# AS3364_waveform_VCA_0402_DIL_v1_0-for_de.net
KiCad netlist of a schematic drawn in EAGLE
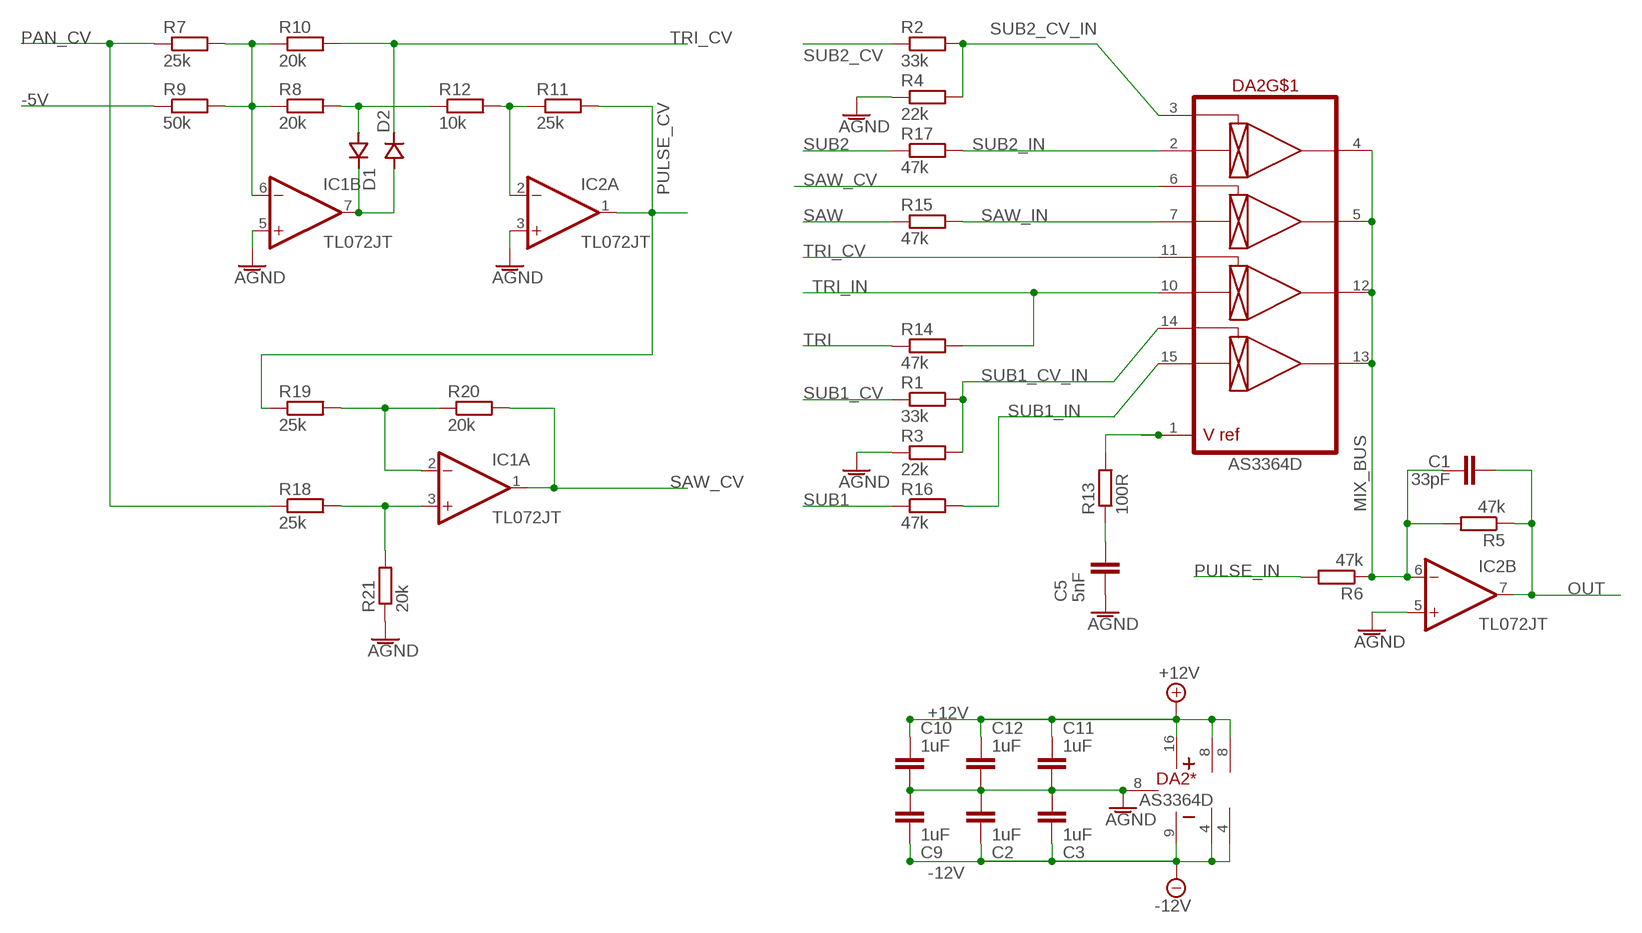
[diagram p0: schematic, sheet 1]

(export (version "E")
  (design (tool "Eeschema 10.0.6"))
  (components
    (comp (ref "C1")
      (value "33pF")
      (footprint "eagle-import:C0402-J")
      (libsource (lib "eagle-import") (part "C-EU-J"))
    )
    (comp (ref "C2")
      (value "1uF")
      (footprint "eagle-import:C0402-J")
      (libsource (lib "eagle-import") (part "C-EU-J"))
    )
    (comp (ref "C3")
      (value "1uF")
      (footprint "eagle-import:C0402-J")
      (libsource (lib "eagle-import") (part "C-EU-J"))
    )
    (comp (ref "C5")
      (value "5nF")
      (footprint "eagle-import:C0402-J")
      (libsource (lib "eagle-import") (part "C-EU-J"))
    )
    (comp (ref "C9")
      (value "1uF")
      (footprint "eagle-import:C0402-J")
      (libsource (lib "eagle-import") (part "C-EU-J"))
    )
    (comp (ref "C10")
      (value "1uF")
      (footprint "eagle-import:C0402-J")
      (libsource (lib "eagle-import") (part "C-EU-J"))
    )
    (comp (ref "C11")
      (value "1uF")
      (footprint "eagle-import:C0402-J")
      (libsource (lib "eagle-import") (part "C-EU-J"))
    )
    (comp (ref "C12")
      (value "1uF")
      (footprint "eagle-import:C0402-J")
      (libsource (lib "eagle-import") (part "C-EU-J"))
    )
    (comp (ref "D1")
      (value "DIODESOD323")
      (footprint "eagle-import:SOD323J")
      (fields (field (name "MPN") "CDSOD323-T05C"))
      (libsource (lib "eagle-import") (part "DIODESOD323"))
    )
    (comp (ref "D2")
      (value "DIODESOD323")
      (footprint "eagle-import:SOD323J")
      (fields (field (name "MPN") "CDSOD323-T05C"))
      (libsource (lib "eagle-import") (part "DIODESOD323"))
    )
    (comp (ref "DA2")
      (value "AS3364D")
      (footprint "eagle-import:DIL16J")
      (libsource (lib "eagle-import") (part "AS3364D"))
    )
    (comp (ref "IC1")
      (value "TL072JT")
      (footprint "eagle-import:TSSOP8J")
      (libsource (lib "eagle-import") (part "TL072JT"))
    )
    (comp (ref "IC2")
      (value "TL072JT")
      (footprint "eagle-import:TSSOP8J")
      (libsource (lib "eagle-import") (part "TL072JT"))
    )
    (comp (ref "R1")
      (value "33k")
      (footprint "eagle-import:R0402")
      (libsource (lib "eagle-import") (part "R-EU_R0402"))
    )
    (comp (ref "R2")
      (value "33k")
      (footprint "eagle-import:R0402")
      (libsource (lib "eagle-import") (part "R-EU_R0402"))
    )
    (comp (ref "R3")
      (value "22k")
      (footprint "eagle-import:R0402")
      (libsource (lib "eagle-import") (part "R-EU_R0402"))
    )
    (comp (ref "R4")
      (value "22k")
      (footprint "eagle-import:R0402")
      (libsource (lib "eagle-import") (part "R-EU_R0402"))
    )
    (comp (ref "R5")
      (value "47k")
      (footprint "eagle-import:R0402")
      (libsource (lib "eagle-import") (part "R-EU_R0402"))
    )
    (comp (ref "R6")
      (value "47k")
      (footprint "eagle-import:R0402")
      (libsource (lib "eagle-import") (part "R-EU_R0402"))
    )
    (comp (ref "R7")
      (value "25k")
      (footprint "eagle-import:R0402")
      (libsource (lib "eagle-import") (part "R-EU_R0402"))
    )
    (comp (ref "R8")
      (value "20k")
      (footprint "eagle-import:R0402")
      (libsource (lib "eagle-import") (part "R-EU_R0402"))
    )
    (comp (ref "R9")
      (value "50k")
      (footprint "eagle-import:R0402")
      (libsource (lib "eagle-import") (part "R-EU_R0402"))
    )
    (comp (ref "R10")
      (value "20k")
      (footprint "eagle-import:R0402")
      (libsource (lib "eagle-import") (part "R-EU_R0402"))
    )
    (comp (ref "R11")
      (value "25k")
      (footprint "eagle-import:R0402")
      (libsource (lib "eagle-import") (part "R-EU_R0402"))
    )
    (comp (ref "R12")
      (value "10k")
      (footprint "eagle-import:R0402")
      (libsource (lib "eagle-import") (part "R-EU_R0402"))
    )
    (comp (ref "R13")
      (value "100R")
      (footprint "eagle-import:R0402")
      (libsource (lib "eagle-import") (part "R-EU_R0402"))
    )
    (comp (ref "R14")
      (value "47k")
      (footprint "eagle-import:R0402")
      (libsource (lib "eagle-import") (part "R-EU_R0402"))
    )
    (comp (ref "R15")
      (value "47k")
      (footprint "eagle-import:R0402")
      (libsource (lib "eagle-import") (part "R-EU_R0402"))
    )
    (comp (ref "R16")
      (value "47k")
      (footprint "eagle-import:R0402")
      (libsource (lib "eagle-import") (part "R-EU_R0402"))
    )
    (comp (ref "R17")
      (value "47k")
      (footprint "eagle-import:R0402")
      (libsource (lib "eagle-import") (part "R-EU_R0402"))
    )
    (comp (ref "R18")
      (value "25k")
      (footprint "eagle-import:R0402")
      (libsource (lib "eagle-import") (part "R-EU_R0402"))
    )
    (comp (ref "R19")
      (value "25k")
      (footprint "eagle-import:R0402")
      (libsource (lib "eagle-import") (part "R-EU_R0402"))
    )
    (comp (ref "R20")
      (value "20k")
      (footprint "eagle-import:R0402")
      (libsource (lib "eagle-import") (part "R-EU_R0402"))
    )
    (comp (ref "R21")
      (value "20k")
      (footprint "eagle-import:R0402")
      (libsource (lib "eagle-import") (part "R-EU_R0402"))
    )
  )
  (nets
    (net (code "1") (name "+12V") (class "Default")
      (node (ref "C10") (pin "2") (pinfunction "2_2") (pintype "passive"))
      (node (ref "C11") (pin "2") (pinfunction "2_2") (pintype "passive"))
      (node (ref "C12") (pin "2") (pinfunction "2_2") (pintype "passive"))
      (node (ref "DA2") (pin "16") (pinfunction "V+_16") (pintype "power_in"))
      (node (ref "IC1") (pin "8") (pinfunction "V+_8") (pintype "power_in"))
      (node (ref "IC2") (pin "8") (pinfunction "V+_8") (pintype "power_in"))
    )
    (net (code "2") (name "-12V") (class "Default")
      (node (ref "C2") (pin "1") (pinfunction "1_1") (pintype "passive"))
      (node (ref "C3") (pin "1") (pinfunction "1_1") (pintype "passive"))
      (node (ref "C9") (pin "1") (pinfunction "1_1") (pintype "passive"))
      (node (ref "DA2") (pin "9") (pinfunction "V-_9") (pintype "power_in"))
      (node (ref "IC1") (pin "4") (pinfunction "V-_4") (pintype "power_in"))
      (node (ref "IC2") (pin "4") (pinfunction "V-_4") (pintype "power_in"))
    )
    (net (code "3") (name "/-5V") (class "Default")
      (node (ref "R9") (pin "1") (pinfunction "1_1") (pintype "passive"))
    )
    (net (code "4") (name "/MIX_BUS") (class "Default")
      (node (ref "C1") (pin "2") (pinfunction "2_2") (pintype "passive"))
      (node (ref "DA2") (pin "12") (pinfunction "OUT3_12") (pintype "output"))
      (node (ref "DA2") (pin "13") (pinfunction "OUT4_13") (pintype "output"))
      (node (ref "DA2") (pin "4") (pinfunction "OUT1_4") (pintype "output"))
      (node (ref "DA2") (pin "5") (pinfunction "OUT2_5") (pintype "output"))
      (node (ref "IC2") (pin "6") (pinfunction "-IN_6") (pintype "input"))
      (node (ref "R5") (pin "2") (pinfunction "2_2") (pintype "passive"))
      (node (ref "R6") (pin "1") (pinfunction "1_1") (pintype "passive"))
    )
    (net (code "5") (name "/OUT") (class "Default")
      (node (ref "C1") (pin "1") (pinfunction "1_1") (pintype "passive"))
      (node (ref "IC2") (pin "7") (pinfunction "OUT_7") (pintype "output"))
      (node (ref "R5") (pin "1") (pinfunction "1_1") (pintype "passive"))
    )
    (net (code "6") (name "/PAN_CV") (class "Default")
      (node (ref "R18") (pin "1") (pinfunction "1_1") (pintype "passive"))
      (node (ref "R7") (pin "1") (pinfunction "1_1") (pintype "passive"))
    )
    (net (code "7") (name "/PULSE_CV") (class "Default")
      (node (ref "IC2") (pin "1") (pinfunction "OUT_1") (pintype "output"))
      (node (ref "R11") (pin "2") (pinfunction "2_2") (pintype "passive"))
      (node (ref "R19") (pin "1") (pinfunction "1_1") (pintype "passive"))
    )
    (net (code "8") (name "/PULSE_IN") (class "Default")
      (node (ref "R6") (pin "2") (pinfunction "2_2") (pintype "passive"))
    )
    (net (code "9") (name "/SAW") (class "Default")
      (node (ref "R15") (pin "1") (pinfunction "1_1") (pintype "passive"))
    )
    (net (code "10") (name "/SAW_CV") (class "Default")
      (node (ref "DA2") (pin "6") (pinfunction "CV2_6") (pintype "input"))
      (node (ref "IC1") (pin "1") (pinfunction "OUT_1") (pintype "output"))
      (node (ref "R20") (pin "2") (pinfunction "2_2") (pintype "passive"))
    )
    (net (code "11") (name "/SAW_IN") (class "Default")
      (node (ref "DA2") (pin "7") (pinfunction "IN2_7") (pintype "input"))
      (node (ref "R15") (pin "2") (pinfunction "2_2") (pintype "passive"))
    )
    (net (code "12") (name "/SUB1") (class "Default")
      (node (ref "R16") (pin "1") (pinfunction "1_1") (pintype "passive"))
    )
    (net (code "13") (name "/SUB1_CV") (class "Default")
      (node (ref "R1") (pin "1") (pinfunction "1_1") (pintype "passive"))
    )
    (net (code "14") (name "/SUB1_CV_IN") (class "Default")
      (node (ref "DA2") (pin "14") (pinfunction "CV4_14") (pintype "input"))
      (node (ref "R1") (pin "2") (pinfunction "2_2") (pintype "passive"))
      (node (ref "R3") (pin "2") (pinfunction "2_2") (pintype "passive"))
    )
    (net (code "15") (name "/SUB1_IN") (class "Default")
      (node (ref "DA2") (pin "15") (pinfunction "IN4_15") (pintype "input"))
      (node (ref "R16") (pin "2") (pinfunction "2_2") (pintype "passive"))
    )
    (net (code "16") (name "/SUB2") (class "Default")
      (node (ref "R17") (pin "1") (pinfunction "1_1") (pintype "passive"))
    )
    (net (code "17") (name "/SUB2_CV") (class "Default")
      (node (ref "R2") (pin "1") (pinfunction "1_1") (pintype "passive"))
    )
    (net (code "18") (name "/SUB2_CV_IN") (class "Default")
      (node (ref "DA2") (pin "3") (pinfunction "CV1_3") (pintype "input"))
      (node (ref "R2") (pin "2") (pinfunction "2_2") (pintype "passive"))
      (node (ref "R4") (pin "2") (pinfunction "2_2") (pintype "passive"))
    )
    (net (code "19") (name "/SUB2_IN") (class "Default")
      (node (ref "DA2") (pin "2") (pinfunction "IN1_2") (pintype "input"))
      (node (ref "R17") (pin "2") (pinfunction "2_2") (pintype "passive"))
    )
    (net (code "20") (name "/TRI") (class "Default")
      (node (ref "R14") (pin "1") (pinfunction "1_1") (pintype "passive"))
    )
    (net (code "21") (name "/TRI_CV") (class "Default")
      (node (ref "D2") (pin "1") (pinfunction "C_1") (pintype "passive"))
      (node (ref "DA2") (pin "11") (pinfunction "CV3_11") (pintype "input"))
      (node (ref "R10") (pin "2") (pinfunction "2_2") (pintype "passive"))
    )
    (net (code "22") (name "/TRI_IN") (class "Default")
      (node (ref "DA2") (pin "10") (pinfunction "IN3_10") (pintype "input"))
      (node (ref "R14") (pin "2") (pinfunction "2_2") (pintype "passive"))
    )
    (net (code "23") (name "AGND") (class "Default")
      (node (ref "C10") (pin "1") (pinfunction "1_1") (pintype "passive"))
      (node (ref "C11") (pin "1") (pinfunction "1_1") (pintype "passive"))
      (node (ref "C12") (pin "1") (pinfunction "1_1") (pintype "passive"))
      (node (ref "C2") (pin "2") (pinfunction "2_2") (pintype "passive"))
      (node (ref "C3") (pin "2") (pinfunction "2_2") (pintype "passive"))
      (node (ref "C5") (pin "1") (pinfunction "1_1") (pintype "passive"))
      (node (ref "C9") (pin "2") (pinfunction "2_2") (pintype "passive"))
      (node (ref "DA2") (pin "8") (pinfunction "GND_8") (pintype "power_in"))
      (node (ref "IC1") (pin "5") (pinfunction "+IN_5") (pintype "input"))
      (node (ref "IC2") (pin "3") (pinfunction "+IN_3") (pintype "input"))
      (node (ref "IC2") (pin "5") (pinfunction "+IN_5") (pintype "input"))
      (node (ref "R21") (pin "1") (pinfunction "1_1") (pintype "passive"))
      (node (ref "R3") (pin "1") (pinfunction "1_1") (pintype "passive"))
      (node (ref "R4") (pin "1") (pinfunction "1_1") (pintype "passive"))
    )
    (net (code "24") (name "Net-(C5-Pad2)") (class "Default")
      (node (ref "C5") (pin "2") (pinfunction "2_2") (pintype "passive"))
      (node (ref "R13") (pin "1") (pinfunction "1_1") (pintype "passive"))
    )
    (net (code "25") (name "Net-(D1-A)") (class "Default")
      (node (ref "D1") (pin "2") (pinfunction "A_2") (pintype "passive"))
      (node (ref "R12") (pin "1") (pinfunction "1_1") (pintype "passive"))
      (node (ref "R8") (pin "2") (pinfunction "2_2") (pintype "passive"))
    )
    (net (code "26") (name "Net-(D1-C)") (class "Default")
      (node (ref "D1") (pin "1") (pinfunction "C_1") (pintype "passive"))
      (node (ref "D2") (pin "2") (pinfunction "A_2") (pintype "passive"))
      (node (ref "IC1") (pin "7") (pinfunction "OUT_7") (pintype "output"))
    )
    (net (code "27") (name "Net-(DA2B-VREF)") (class "Default")
      (node (ref "DA2") (pin "1") (pinfunction "VREF_1") (pintype "output"))
      (node (ref "R13") (pin "2") (pinfunction "2_2") (pintype "passive"))
    )
    (net (code "28") (name "Net-(IC1A-+IN)") (class "Default")
      (node (ref "IC1") (pin "3") (pinfunction "+IN_3") (pintype "input"))
      (node (ref "R18") (pin "2") (pinfunction "2_2") (pintype "passive"))
      (node (ref "R21") (pin "2") (pinfunction "2_2") (pintype "passive"))
    )
    (net (code "29") (name "Net-(IC1A--IN)") (class "Default")
      (node (ref "IC1") (pin "2") (pinfunction "-IN_2") (pintype "input"))
      (node (ref "R19") (pin "2") (pinfunction "2_2") (pintype "passive"))
      (node (ref "R20") (pin "1") (pinfunction "1_1") (pintype "passive"))
    )
    (net (code "30") (name "Net-(IC1B--IN)") (class "Default")
      (node (ref "IC1") (pin "6") (pinfunction "-IN_6") (pintype "input"))
      (node (ref "R10") (pin "1") (pinfunction "1_1") (pintype "passive"))
      (node (ref "R7") (pin "2") (pinfunction "2_2") (pintype "passive"))
      (node (ref "R8") (pin "1") (pinfunction "1_1") (pintype "passive"))
      (node (ref "R9") (pin "2") (pinfunction "2_2") (pintype "passive"))
    )
    (net (code "31") (name "Net-(IC2A--IN)") (class "Default")
      (node (ref "IC2") (pin "2") (pinfunction "-IN_2") (pintype "input"))
      (node (ref "R11") (pin "1") (pinfunction "1_1") (pintype "passive"))
      (node (ref "R12") (pin "2") (pinfunction "2_2") (pintype "passive"))
    )
  )
)
